# v1_1.net
KiCad netlist of a schematic drawn in EAGLE
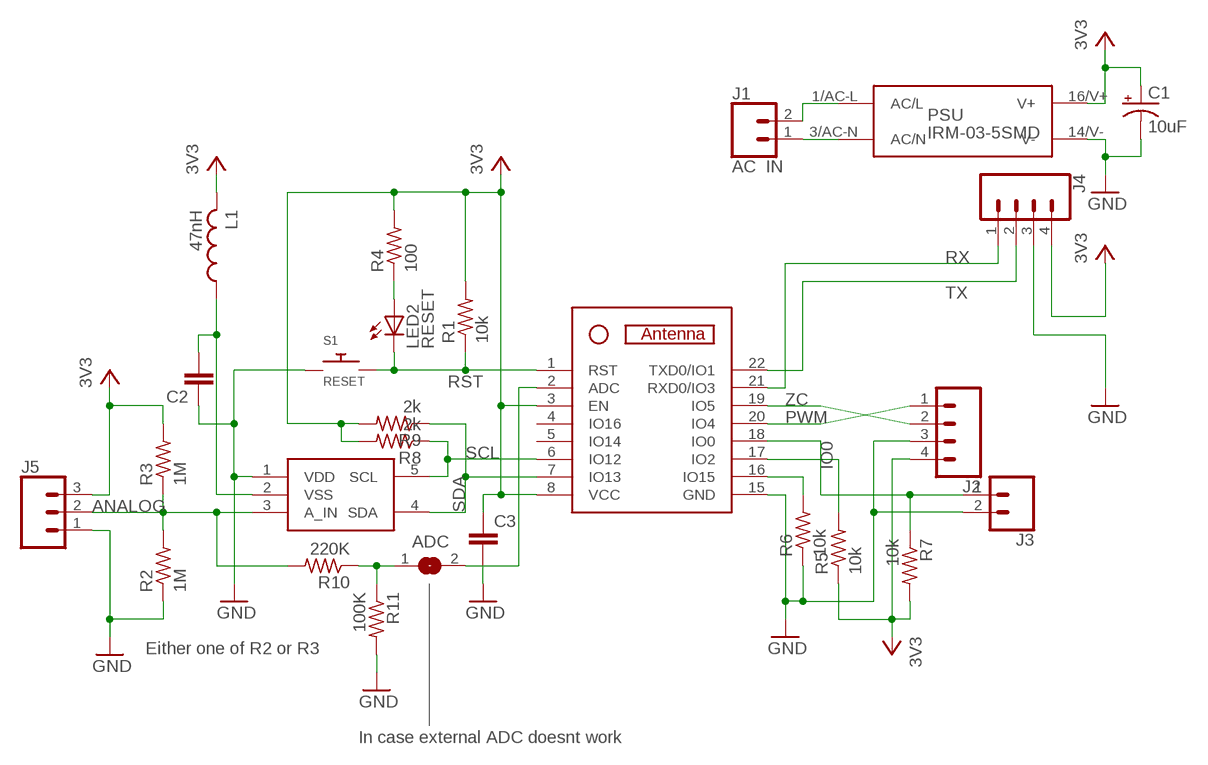
[diagram p0: schematic, sheet 1]

(export (version "E")
  (design (tool "Eeschema 10.0.6"))
  (components
    (comp (ref "ADC") (value "SJ") (footprint "eagle-import:SJ") (libsource (lib "eagle-import") (part "SJ")))
    (comp (ref "C1")
      (value "10uF")
      (footprint "eagle-import:153CLV-0405")
      (libsource (lib "eagle-import") (part "CPOL-US153CLV-0405"))
    )
    (comp (ref "C2")
      (value "C-EUC0805")
      (footprint "eagle-import:C0805")
      (libsource (lib "eagle-import") (part "C-EUC0805"))
    )
    (comp (ref "C3")
      (value "C-EUC0805")
      (footprint "eagle-import:C0805")
      (libsource (lib "eagle-import") (part "C-EUC0805"))
    )
    (comp (ref "J1")
      (value "AC IN")
      (footprint "eagle-import:1X2_5MM_SCREW")
      (libsource (lib "eagle-import") (part "1X2_5MM_SCREW"))
    )
    (comp (ref "J2")
      (value "CONN_04")
      (footprint "eagle-import:1X04")
      (libsource (lib "eagle-import") (part "CONN_04"))
    )
    (comp (ref "J3")
      (value "CONN_02")
      (footprint "eagle-import:1X02")
      (libsource (lib "eagle-import") (part "CONN_02"))
    )
    (comp (ref "J4")
      (value "CONN_04")
      (footprint "eagle-import:1X04")
      (libsource (lib "eagle-import") (part "CONN_04"))
    )
    (comp (ref "J5")
      (value "CONN_03")
      (footprint "eagle-import:1X03")
      (libsource (lib "eagle-import") (part "CONN_03"))
    )
    (comp (ref "L1")
      (value "47nH")
      (footprint "eagle-import:L2012C")
      (libsource (lib "eagle-import") (part "L-USL2012C"))
    )
    (comp (ref "LED2")
      (value "RESET")
      (footprint "eagle-import:SML0805")
      (libsource (lib "eagle-import") (part "LEDSML0805"))
    )
    (comp (ref "PSU")
      (value "IRM-03-5SMD")
      (footprint "eagle-import:IRM-03-5S")
      (libsource (lib "eagle-import") (part "IRM-03-5SMD"))
    )
    (comp (ref "R1")
      (value "10k")
      (footprint "eagle-import:R0603")
      (libsource (lib "eagle-import") (part "R-US_R0603"))
    )
    (comp (ref "R2")
      (value "1M")
      (footprint "eagle-import:R0603")
      (libsource (lib "eagle-import") (part "R-US_R0603"))
    )
    (comp (ref "R3")
      (value "1M")
      (footprint "eagle-import:R0603")
      (libsource (lib "eagle-import") (part "R-US_R0603"))
    )
    (comp (ref "R4")
      (value "100")
      (footprint "eagle-import:R0805")
      (libsource (lib "eagle-import") (part "R-US_R0805"))
    )
    (comp (ref "R5")
      (value "10k")
      (footprint "eagle-import:R0603")
      (libsource (lib "eagle-import") (part "R-US_R0603"))
    )
    (comp (ref "R6")
      (value "10k")
      (footprint "eagle-import:R0603")
      (libsource (lib "eagle-import") (part "R-US_R0603"))
    )
    (comp (ref "R7")
      (value "10k")
      (footprint "eagle-import:R0603")
      (libsource (lib "eagle-import") (part "R-US_R0603"))
    )
    (comp (ref "R8")
      (value "2k")
      (footprint "eagle-import:R0603")
      (libsource (lib "eagle-import") (part "R-US_R0603"))
    )
    (comp (ref "R9")
      (value "2k")
      (footprint "eagle-import:R0603")
      (libsource (lib "eagle-import") (part "R-US_R0603"))
    )
    (comp (ref "R10")
      (value "220K")
      (footprint "eagle-import:R0603")
      (libsource (lib "eagle-import") (part "R-US_R0603"))
    )
    (comp (ref "R11")
      (value "100K")
      (footprint "eagle-import:R0603")
      (libsource (lib "eagle-import") (part "R-US_R0603"))
    )
    (comp (ref "S1")
      (value "RESET")
      (footprint "eagle-import:TACTILE_SWITCH_SMD_6.2MM_TALL")
      (libsource (lib "eagle-import") (part "BUTTON"))
    )
    (comp (ref "U1")
      (value "ESP-07")
      (footprint "eagle-import:ESP-07")
      (libsource (lib "eagle-import") (part "ESP-07"))
    )
    (comp (ref "U2")
      (value "MCP3221")
      (footprint "eagle-import:SOT23-5")
      (libsource (lib "eagle-import") (part "MCP3221"))
    )
  )
  (nets
    (net (code "1") (name "/ANALOG") (class "Default")
      (node (ref "J5") (pin "2") (pinfunction "2_2") (pintype "passive"))
      (node (ref "R10") (pin "2") (pinfunction "2_2") (pintype "passive"))
      (node (ref "R2") (pin "2") (pinfunction "2_2") (pintype "passive"))
      (node (ref "R3") (pin "1") (pinfunction "1_1") (pintype "passive"))
      (node (ref "U2") (pin "3") (pinfunction "A_IN_3") (pintype "bidirectional"))
    )
    (net (code "2") (name "/IO0") (class "Default")
      (node (ref "J3") (pin "1") (pinfunction "1_1") (pintype "passive"))
      (node (ref "R7") (pin "1") (pinfunction "1_1") (pintype "passive"))
      (node (ref "U1") (pin "18") (pinfunction "IO0_18") (pintype "bidirectional"))
    )
    (net (code "3") (name "/PWM") (class "Default")
      (node (ref "J2") (pin "1") (pinfunction "1_1") (pintype "passive"))
      (node (ref "U1") (pin "20") (pinfunction "IO4_20") (pintype "bidirectional"))
    )
    (net (code "4") (name "/RST") (class "Default")
      (node (ref "LED2") (pin "C") (pinfunction "C_C") (pintype "passive"))
      (node (ref "R1") (pin "1") (pinfunction "1_1") (pintype "passive"))
      (node (ref "S1") (pin "B1") (pinfunction "P$2_B1") (pintype "passive"))
      (node (ref "S1") (pin "B2") (pinfunction "P$2_B2") (pintype "passive"))
      (node (ref "U1") (pin "1") (pinfunction "RST_1") (pintype "bidirectional"))
    )
    (net (code "5") (name "/RX") (class "Default")
      (node (ref "J4") (pin "1") (pinfunction "1_1") (pintype "passive"))
      (node (ref "U1") (pin "21") (pinfunction "RXD0/IO3_21") (pintype "bidirectional"))
    )
    (net (code "6") (name "/SCL") (class "Default")
      (node (ref "R8") (pin "1") (pinfunction "1_1") (pintype "passive"))
      (node (ref "U1") (pin "6") (pinfunction "IO12_6") (pintype "bidirectional"))
      (node (ref "U2") (pin "5") (pinfunction "SCL_5") (pintype "bidirectional"))
    )
    (net (code "7") (name "/SDA") (class "Default")
      (node (ref "R9") (pin "1") (pinfunction "1_1") (pintype "passive"))
      (node (ref "U1") (pin "7") (pinfunction "IO13_7") (pintype "bidirectional"))
      (node (ref "U2") (pin "4") (pinfunction "SDA_4") (pintype "bidirectional"))
    )
    (net (code "8") (name "/TX") (class "Default")
      (node (ref "J4") (pin "2") (pinfunction "2_2") (pintype "passive"))
      (node (ref "U1") (pin "22") (pinfunction "TXD0/IO1_22") (pintype "bidirectional"))
    )
    (net (code "9") (name "/ZC") (class "Default")
      (node (ref "J2") (pin "2") (pinfunction "2_2") (pintype "passive"))
      (node (ref "U1") (pin "19") (pinfunction "IO5_19") (pintype "bidirectional"))
    )
    (net (code "10") (name "3V3") (class "Default")
      (node (ref "C1") (pin "+") (pinfunction "+_+") (pintype "passive"))
      (node (ref "C3") (pin "1") (pinfunction "1_1") (pintype "passive"))
      (node (ref "J2") (pin "4") (pinfunction "4_4") (pintype "passive"))
      (node (ref "J4") (pin "4") (pinfunction "4_4") (pintype "passive"))
      (node (ref "J5") (pin "3") (pinfunction "3_3") (pintype "passive"))
      (node (ref "L1") (pin "2") (pinfunction "2_2") (pintype "passive"))
      (node (ref "PSU") (pin "16/V+") (pinfunction "V+_16/V+") (pintype "bidirectional"))
      (node (ref "R1") (pin "2") (pinfunction "2_2") (pintype "passive"))
      (node (ref "R3") (pin "2") (pinfunction "2_2") (pintype "passive"))
      (node (ref "R4") (pin "2") (pinfunction "2_2") (pintype "passive"))
      (node (ref "R5") (pin "1") (pinfunction "1_1") (pintype "passive"))
      (node (ref "R7") (pin "2") (pinfunction "2_2") (pintype "passive"))
      (node (ref "R8") (pin "2") (pinfunction "2_2") (pintype "passive"))
      (node (ref "R9") (pin "2") (pinfunction "2_2") (pintype "passive"))
      (node (ref "U1") (pin "3") (pinfunction "EN_3") (pintype "bidirectional"))
      (node (ref "U1") (pin "8") (pinfunction "VCC_8") (pintype "bidirectional"))
    )
    (net (code "11") (name "GND") (class "Default")
      (node (ref "C1") (pin "-") (pinfunction "-_-") (pintype "passive"))
      (node (ref "C2") (pin "1") (pinfunction "1_1") (pintype "passive"))
      (node (ref "C3") (pin "2") (pinfunction "2_2") (pintype "passive"))
      (node (ref "J2") (pin "3") (pinfunction "3_3") (pintype "passive"))
      (node (ref "J3") (pin "2") (pinfunction "2_2") (pintype "passive"))
      (node (ref "J4") (pin "3") (pinfunction "3_3") (pintype "passive"))
      (node (ref "J5") (pin "1") (pinfunction "1_1") (pintype "passive"))
      (node (ref "PSU") (pin "14/V-") (pinfunction "V-_14/V-") (pintype "bidirectional"))
      (node (ref "R11") (pin "2") (pinfunction "2_2") (pintype "passive"))
      (node (ref "R2") (pin "1") (pinfunction "1_1") (pintype "passive"))
      (node (ref "R6") (pin "1") (pinfunction "1_1") (pintype "passive"))
      (node (ref "S1") (pin "A1") (pinfunction "P$1_A1") (pintype "passive"))
      (node (ref "S1") (pin "A2") (pinfunction "P$1_A2") (pintype "passive"))
      (node (ref "U1") (pin "15") (pinfunction "GND_15") (pintype "bidirectional"))
      (node (ref "U2") (pin "1") (pinfunction "VDD_1") (pintype "bidirectional"))
    )
    (net (code "12") (name "Net-(ADC-Pad1)") (class "Default")
      (node (ref "ADC") (pin "1") (pinfunction "1_1") (pintype "passive"))
      (node (ref "R10") (pin "1") (pinfunction "1_1") (pintype "passive"))
      (node (ref "R11") (pin "1") (pinfunction "1_1") (pintype "passive"))
    )
    (net (code "13") (name "Net-(LED2-PadA)") (class "Default")
      (node (ref "LED2") (pin "A") (pinfunction "A_A") (pintype "passive"))
      (node (ref "R4") (pin "1") (pinfunction "1_1") (pintype "passive"))
    )
    (net (code "14") (name "Net-(PSU-AC{slash}L)") (class "Default")
      (node (ref "J1") (pin "2") (pinfunction "2_2") (pintype "passive"))
      (node (ref "PSU") (pin "1/AC-L") (pinfunction "AC/L_1/AC-L") (pintype "bidirectional"))
    )
    (net (code "15") (name "Net-(PSU-AC{slash}N)") (class "Default")
      (node (ref "J1") (pin "1") (pinfunction "1_1") (pintype "passive"))
      (node (ref "PSU") (pin "3/AC-N") (pinfunction "AC/N_3/AC-N") (pintype "bidirectional"))
    )
    (net (code "16") (name "Net-(U1-ADC)") (class "Default")
      (node (ref "ADC") (pin "2") (pinfunction "2_2") (pintype "passive"))
      (node (ref "U1") (pin "2") (pinfunction "ADC_2") (pintype "bidirectional"))
    )
    (net (code "17") (name "Net-(U1-IO2)") (class "Default")
      (node (ref "R5") (pin "2") (pinfunction "2_2") (pintype "passive"))
      (node (ref "U1") (pin "17") (pinfunction "IO2_17") (pintype "bidirectional"))
    )
    (net (code "18") (name "Net-(U1-IO15)") (class "Default")
      (node (ref "R6") (pin "2") (pinfunction "2_2") (pintype "passive"))
      (node (ref "U1") (pin "16") (pinfunction "IO15_16") (pintype "bidirectional"))
    )
    (net (code "19") (name "Net-(U2-VSS)") (class "Default")
      (node (ref "C2") (pin "2") (pinfunction "2_2") (pintype "passive"))
      (node (ref "L1") (pin "1") (pinfunction "1_1") (pintype "passive"))
      (node (ref "U2") (pin "2") (pinfunction "VSS_2") (pintype "bidirectional"))
    )
    (net (code "20") (name "unconnected-(U1-IO14-Pad5)") (class "Default")
      (node (ref "U1") (pin "5") (pinfunction "IO14_5") (pintype "bidirectional"))
    )
    (net (code "21") (name "unconnected-(U1-IO16-Pad4)") (class "Default")
      (node (ref "U1") (pin "4") (pinfunction "IO16_4") (pintype "bidirectional"))
    )
  )
)
